# OAmp_TestBoard.net
KiCad netlist of a schematic drawn in Altium Designer
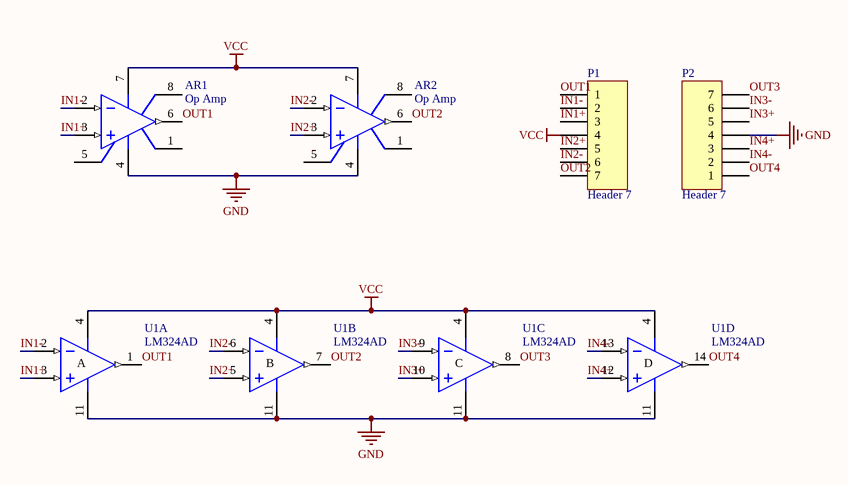
[diagram p0: OAmp_TestBoard.SchDoc]

(export (version "E")
  (design (tool "Eeschema 10.0.6"))
  (components
    (comp (ref "AR1")
      (value "Op Amp")
      (footprint "SOT-23-OT5_N")
      (description "FET Operational Amplifier")
      (fields (field (name "PUBLISHER") "Altium Limited"))
      (libsource (lib "Miscellaneous Devices") (part "Op Amp"))
    )
    (comp (ref "AR2")
      (value "Op Amp")
      (footprint "SOT-23-OT5_N")
      (description "FET Operational Amplifier")
      (fields (field (name "PUBLISHER") "Altium Limited"))
      (libsource (lib "Miscellaneous Devices") (part "Op Amp"))
    )
    (comp (ref "P1")
      (value "Header 7")
      (footprint "HDR1X7")
      (description "Header, 7-Pin")
      (fields (field (name "PUBLISHER") "Altium Limited"))
      (libsource (lib "Miscellaneous Connectors") (part "Header 7"))
    )
    (comp (ref "P2")
      (value "Header 7")
      (footprint "HDR1X7")
      (description "Header, 7-Pin")
      (fields (field (name "PUBLISHER") "Altium Limited"))
      (libsource (lib "") (part "Header 7_1"))
    )
    (comp (ref "U1")
      (value "LM324AD")
      (footprint "SO14_N")
      (description "Low-Power Quad Operational Amplifier")
      (fields (field (name "PUBLISHER") "Altium Limited"))
      (libsource (lib "ST Operational Amplifier") (part "LM324AD"))
    )
  )
  (nets
    (net (code "1") (name "/IN1+") (class "Default")
      (node (ref "AR1") (pin "3") (pinfunction "IN+_3") (pintype "input"))
      (node (ref "P1") (pin "3") (pinfunction "3_3") (pintype "passive"))
      (node (ref "U1") (pin "3") (pinfunction "IN+_3") (pintype "input"))
    )
    (net (code "2") (name "/IN1-") (class "Default")
      (node (ref "AR1") (pin "2") (pinfunction "IN-_2") (pintype "input"))
      (node (ref "P1") (pin "2") (pinfunction "2_2") (pintype "passive"))
      (node (ref "U1") (pin "2") (pinfunction "IN-_2") (pintype "input"))
    )
    (net (code "3") (name "/IN2+") (class "Default")
      (node (ref "AR2") (pin "3") (pinfunction "IN+_3") (pintype "input"))
      (node (ref "P1") (pin "5") (pinfunction "5_5") (pintype "passive"))
      (node (ref "U1") (pin "5") (pinfunction "IN+_5") (pintype "input"))
    )
    (net (code "4") (name "/IN2-") (class "Default")
      (node (ref "AR2") (pin "2") (pinfunction "IN-_2") (pintype "input"))
      (node (ref "P1") (pin "6") (pinfunction "6_6") (pintype "passive"))
      (node (ref "U1") (pin "6") (pinfunction "IN-_6") (pintype "input"))
    )
    (net (code "5") (name "/IN3+") (class "Default")
      (node (ref "P2") (pin "5") (pinfunction "5_5") (pintype "passive"))
      (node (ref "U1") (pin "10") (pinfunction "IN+_10") (pintype "input"))
    )
    (net (code "6") (name "/IN3-") (class "Default")
      (node (ref "P2") (pin "6") (pinfunction "6_6") (pintype "passive"))
      (node (ref "U1") (pin "9") (pinfunction "IN-_9") (pintype "input"))
    )
    (net (code "7") (name "/IN4+") (class "Default")
      (node (ref "P2") (pin "3") (pinfunction "3_3") (pintype "passive"))
      (node (ref "U1") (pin "12") (pinfunction "IN+_12") (pintype "input"))
    )
    (net (code "8") (name "/IN4-") (class "Default")
      (node (ref "P2") (pin "2") (pinfunction "2_2") (pintype "passive"))
      (node (ref "U1") (pin "13") (pinfunction "IN-_13") (pintype "input"))
    )
    (net (code "9") (name "/OUT1") (class "Default")
      (node (ref "AR1") (pin "6") (pinfunction "OUT_6") (pintype "output"))
      (node (ref "P1") (pin "1") (pinfunction "1_1") (pintype "passive"))
      (node (ref "U1") (pin "1") (pinfunction "OUT_1") (pintype "output"))
    )
    (net (code "10") (name "/OUT2") (class "Default")
      (node (ref "AR2") (pin "6") (pinfunction "OUT_6") (pintype "output"))
      (node (ref "P1") (pin "7") (pinfunction "7_7") (pintype "passive"))
      (node (ref "U1") (pin "7") (pinfunction "OUT_7") (pintype "output"))
    )
    (net (code "11") (name "/OUT3") (class "Default")
      (node (ref "P2") (pin "7") (pinfunction "7_7") (pintype "passive"))
      (node (ref "U1") (pin "8") (pinfunction "OUT_8") (pintype "output"))
    )
    (net (code "12") (name "/OUT4") (class "Default")
      (node (ref "P2") (pin "1") (pinfunction "1_1") (pintype "passive"))
      (node (ref "U1") (pin "14") (pinfunction "OUT_14") (pintype "output"))
    )
    (net (code "13") (name "GND") (class "Default")
      (node (ref "AR1") (pin "4") (pinfunction "V-_4") (pintype "power_in"))
      (node (ref "AR2") (pin "4") (pinfunction "V-_4") (pintype "power_in"))
      (node (ref "P2") (pin "4") (pinfunction "4_4") (pintype "passive"))
      (node (ref "U1") (pin "11") (pinfunction "V-_11") (pintype "power_in"))
    )
    (net (code "14") (name "VCC") (class "Default")
      (node (ref "AR1") (pin "7") (pinfunction "V+_7") (pintype "power_in"))
      (node (ref "AR2") (pin "7") (pinfunction "V+_7") (pintype "power_in"))
      (node (ref "P1") (pin "4") (pinfunction "4_4") (pintype "passive"))
      (node (ref "U1") (pin "4") (pinfunction "V+_4") (pintype "power_in"))
    )
    (net (code "15") (name "unconnected-(AR1-OS_NUL-Pad1)") (class "Default")
      (node (ref "AR1") (pin "1") (pinfunction "OS_NUL_1") (pintype "passive"))
    )
    (net (code "16") (name "unconnected-(AR1-OS_NUL-Pad5)") (class "Default")
      (node (ref "AR1") (pin "5") (pinfunction "OS_NUL_5") (pintype "passive"))
    )
    (net (code "17") (name "unconnected-(AR1-TAB-Pad8)") (class "Default")
      (node (ref "AR1") (pin "8") (pinfunction "TAB_8") (pintype "passive"))
    )
    (net (code "18") (name "unconnected-(AR2-OS_NUL-Pad1)") (class "Default")
      (node (ref "AR2") (pin "1") (pinfunction "OS_NUL_1") (pintype "passive"))
    )
    (net (code "19") (name "unconnected-(AR2-OS_NUL-Pad5)") (class "Default")
      (node (ref "AR2") (pin "5") (pinfunction "OS_NUL_5") (pintype "passive"))
    )
    (net (code "20") (name "unconnected-(AR2-TAB-Pad8)") (class "Default")
      (node (ref "AR2") (pin "8") (pinfunction "TAB_8") (pintype "passive"))
    )
  )
)
